# LV_supplies.net
KiCad netlist of a schematic drawn in Altium Designer
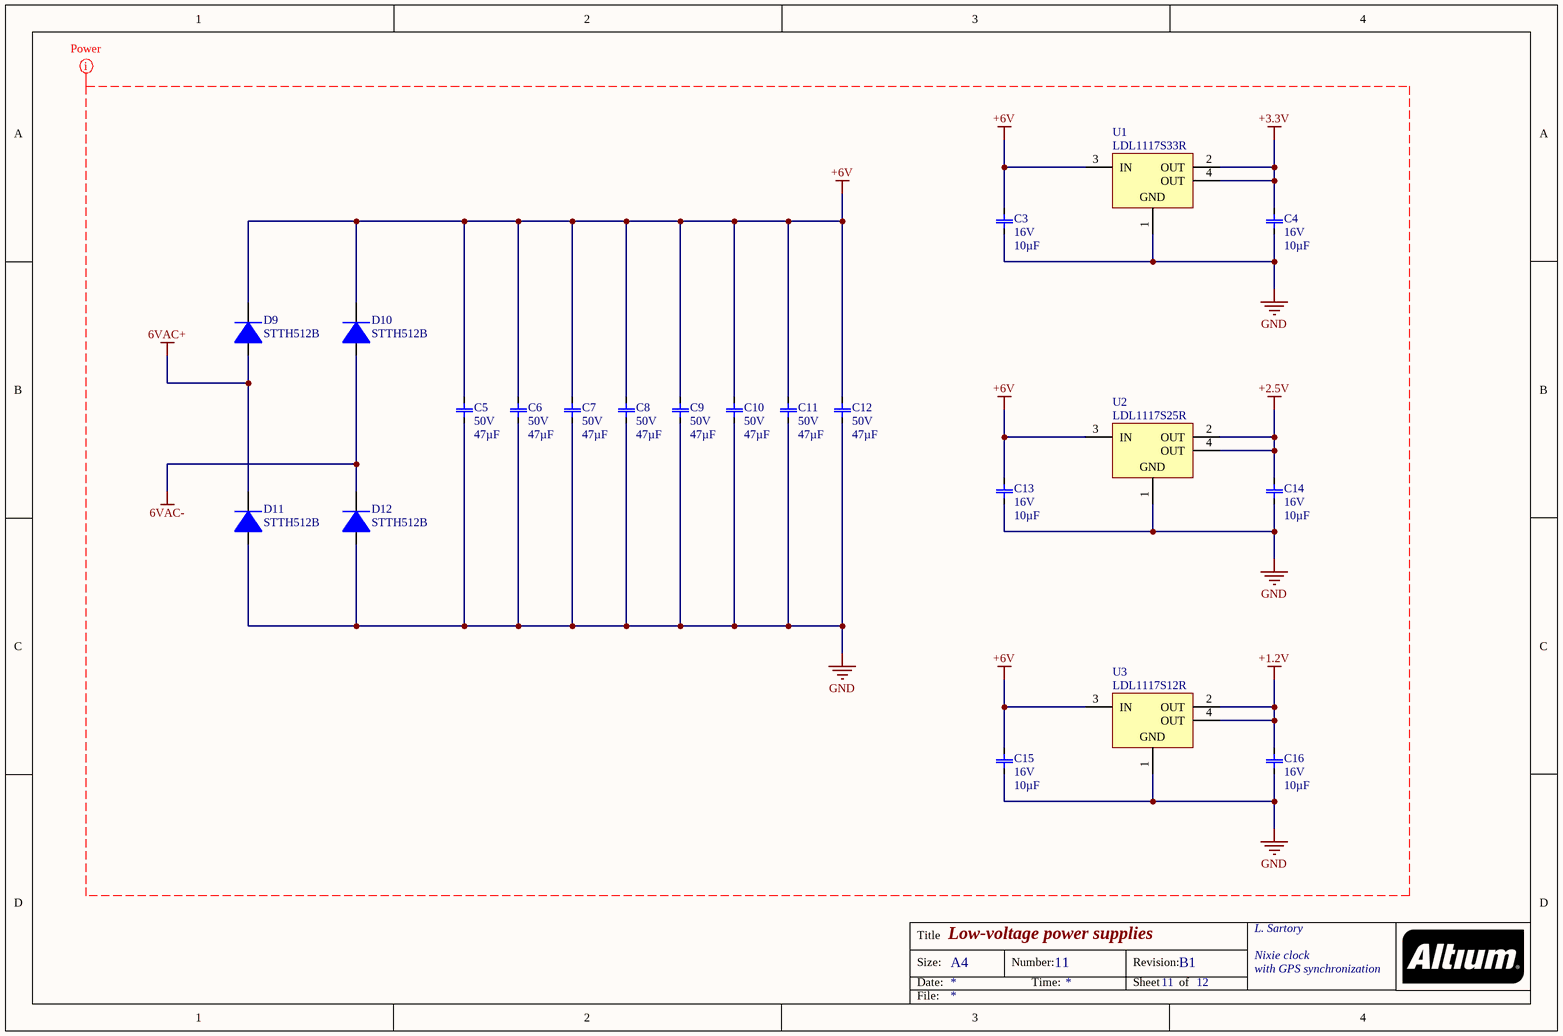
[diagram p0: LV_supplies.SchDoc]

(export (version "E")
  (design (tool "Eeschema 10.0.6"))
  (components
    (comp (ref "C3")
      (value "10µF")
      (footprint "MLCC_1210")
      (description "MLCC 10µF 16V 1210")
      (fields (field (name "VOLTAGE") "16V"))
      (libsource (lib "Nixie") (part "MLCC 10µF 16V 1210"))
    )
    (comp (ref "C4")
      (value "10µF")
      (footprint "MLCC_1210")
      (description "MLCC 10µF 16V 1210")
      (fields (field (name "VOLTAGE") "16V"))
      (libsource (lib "Nixie") (part "MLCC 10µF 16V 1210"))
    )
    (comp (ref "C5")
      (value "47µF")
      (footprint "MLCC_1210")
      (description "MLCC 47µF 50V 1210")
      (fields (field (name "VOLTAGE") "50V"))
      (libsource (lib "Nixie") (part "MLCC 47µF 50V 1210"))
    )
    (comp (ref "C6")
      (value "47µF")
      (footprint "MLCC_1210")
      (description "MLCC 47µF 50V 1210")
      (fields (field (name "VOLTAGE") "50V"))
      (libsource (lib "Nixie") (part "MLCC 47µF 50V 1210"))
    )
    (comp (ref "C7")
      (value "47µF")
      (footprint "MLCC_1210")
      (description "MLCC 47µF 50V 1210")
      (fields (field (name "VOLTAGE") "50V"))
      (libsource (lib "Nixie") (part "MLCC 47µF 50V 1210"))
    )
    (comp (ref "C8")
      (value "47µF")
      (footprint "MLCC_1210")
      (description "MLCC 47µF 50V 1210")
      (fields (field (name "VOLTAGE") "50V"))
      (libsource (lib "Nixie") (part "MLCC 47µF 50V 1210"))
    )
    (comp (ref "C9")
      (value "47µF")
      (footprint "MLCC_1210")
      (description "MLCC 47µF 50V 1210")
      (fields (field (name "VOLTAGE") "50V"))
      (libsource (lib "Nixie") (part "MLCC 47µF 50V 1210"))
    )
    (comp (ref "C10")
      (value "47µF")
      (footprint "MLCC_1210")
      (description "MLCC 47µF 50V 1210")
      (fields (field (name "VOLTAGE") "50V"))
      (libsource (lib "Nixie") (part "MLCC 47µF 50V 1210"))
    )
    (comp (ref "C11")
      (value "47µF")
      (footprint "MLCC_1210")
      (description "MLCC 47µF 50V 1210")
      (fields (field (name "VOLTAGE") "50V"))
      (libsource (lib "Nixie") (part "MLCC 47µF 50V 1210"))
    )
    (comp (ref "C12")
      (value "47µF")
      (footprint "MLCC_1210")
      (description "MLCC 47µF 50V 1210")
      (fields (field (name "VOLTAGE") "50V"))
      (libsource (lib "Nixie") (part "MLCC 47µF 50V 1210"))
    )
    (comp (ref "C13")
      (value "10µF")
      (footprint "MLCC_1210")
      (description "MLCC 10µF 16V 1210")
      (fields (field (name "VOLTAGE") "16V"))
      (libsource (lib "Nixie") (part "MLCC 10µF 16V 1210"))
    )
    (comp (ref "C14")
      (value "10µF")
      (footprint "MLCC_1210")
      (description "MLCC 10µF 16V 1210")
      (fields (field (name "VOLTAGE") "16V"))
      (libsource (lib "Nixie") (part "MLCC 10µF 16V 1210"))
    )
    (comp (ref "C15")
      (value "10µF")
      (footprint "MLCC_1210")
      (description "MLCC 10µF 16V 1210")
      (fields (field (name "VOLTAGE") "16V"))
      (libsource (lib "Nixie") (part "MLCC 10µF 16V 1210"))
    )
    (comp (ref "C16")
      (value "10µF")
      (footprint "MLCC_1210")
      (description "MLCC 10µF 16V 1210")
      (fields (field (name "VOLTAGE") "16V"))
      (libsource (lib "Nixie") (part "MLCC 10µF 16V 1210"))
    )
    (comp (ref "D9")
      (value "STTH512B")
      (footprint "STTH512B")
      (description "Ultrafast recovery - 1200 V diode")
      (libsource (lib "Nixie") (part "STTH512B"))
    )
    (comp (ref "D10")
      (value "STTH512B")
      (footprint "STTH512B")
      (description "Ultrafast recovery - 1200 V diode")
      (libsource (lib "Nixie") (part "STTH512B"))
    )
    (comp (ref "D11")
      (value "STTH512B")
      (footprint "STTH512B")
      (description "Ultrafast recovery - 1200 V diode")
      (libsource (lib "Nixie") (part "STTH512B"))
    )
    (comp (ref "D12")
      (value "STTH512B")
      (footprint "STTH512B")
      (description "Ultrafast recovery - 1200 V diode")
      (libsource (lib "Nixie") (part "STTH512B"))
    )
    (comp (ref "U1")
      (value "LDL1117S33R")
      (footprint "TLV1117")
      (description "Fixed LDO Voltage Regulator, 2.6 V to 18 V input, 75 mV Dropout, 3.3 V / 1.2 A out, SOT-223-4")
      (fields (field (name "PARTNUMBER") "TLV1117LV12DCYT") (field (name "MANUFACTURER") "Texas Instruments"))
      (libsource (lib "Nixie") (part "LDL1117S33R"))
    )
    (comp (ref "U2")
      (value "LDL1117S25R")
      (footprint "TLV1117")
      (description "Fixed LDO Voltage Regulator, 2.6 V to 18 V input, 75 mV Dropout, 2.5 V / 1.2 A out, SOT-223-4")
      (fields (field (name "MANUFACTURER") "Texas Instruments") (field (name "PARTNUMBER") "TLV1117LV25DCYT"))
      (libsource (lib "Nixie") (part "LDL1117S25R"))
    )
    (comp (ref "U3")
      (value "LDL1117S12R")
      (footprint "TLV1117")
      (description "Fixed LDO Voltage Regulator, 2.6 V to 18 V input, 170 mV Dropout, 1.2 V / 1.2 A out, SOT-223-4")
      (fields (field (name "MANUFACTURER") "Texas Instruments") (field (name "PARTNUMBER") "TLV1117LV30DCYT"))
      (libsource (lib "Nixie") (part "LDL1117S12R"))
    )
  )
  (nets
    (net (code "1") (name "+1.2V") (class "Default")
      (node (ref "C16") (pin "2") (pinfunction "2_2") (pintype "passive"))
      (node (ref "U3") (pin "2") (pinfunction "OUT_2") (pintype "power_in"))
      (node (ref "U3") (pin "4") (pinfunction "OUT_4") (pintype "power_in"))
    )
    (net (code "2") (name "+2.5V") (class "Default")
      (node (ref "C14") (pin "2") (pinfunction "2_2") (pintype "passive"))
      (node (ref "U2") (pin "2") (pinfunction "OUT_2") (pintype "power_in"))
      (node (ref "U2") (pin "4") (pinfunction "OUT_4") (pintype "power_in"))
    )
    (net (code "3") (name "+3.3V") (class "Default")
      (node (ref "C4") (pin "2") (pinfunction "2_2") (pintype "passive"))
      (node (ref "U1") (pin "2") (pinfunction "OUT_2") (pintype "power_in"))
      (node (ref "U1") (pin "4") (pinfunction "OUT_4") (pintype "power_in"))
    )
    (net (code "4") (name "+6V") (class "Default")
      (node (ref "C10") (pin "2") (pinfunction "2_2") (pintype "passive"))
      (node (ref "C11") (pin "2") (pinfunction "2_2") (pintype "passive"))
      (node (ref "C12") (pin "2") (pinfunction "2_2") (pintype "passive"))
      (node (ref "C13") (pin "2") (pinfunction "2_2") (pintype "passive"))
      (node (ref "C15") (pin "2") (pinfunction "2_2") (pintype "passive"))
      (node (ref "C3") (pin "2") (pinfunction "2_2") (pintype "passive"))
      (node (ref "C5") (pin "2") (pinfunction "2_2") (pintype "passive"))
      (node (ref "C6") (pin "2") (pinfunction "2_2") (pintype "passive"))
      (node (ref "C7") (pin "2") (pinfunction "2_2") (pintype "passive"))
      (node (ref "C8") (pin "2") (pinfunction "2_2") (pintype "passive"))
      (node (ref "C9") (pin "2") (pinfunction "2_2") (pintype "passive"))
      (node (ref "D10") (pin "K") (pinfunction "K_K") (pintype "passive"))
      (node (ref "D9") (pin "K") (pinfunction "K_K") (pintype "passive"))
      (node (ref "U1") (pin "3") (pinfunction "IN_3") (pintype "power_in"))
      (node (ref "U2") (pin "3") (pinfunction "IN_3") (pintype "power_in"))
      (node (ref "U3") (pin "3") (pinfunction "IN_3") (pintype "power_in"))
    )
    (net (code "5") (name "6VAC+") (class "Default")
      (node (ref "D11") (pin "K") (pinfunction "K_K") (pintype "passive"))
      (node (ref "D9") (pin "A") (pinfunction "A_A") (pintype "passive"))
    )
    (net (code "6") (name "6VAC-") (class "Default")
      (node (ref "D10") (pin "A") (pinfunction "A_A") (pintype "passive"))
      (node (ref "D12") (pin "K") (pinfunction "K_K") (pintype "passive"))
    )
    (net (code "7") (name "GND") (class "Default")
      (node (ref "C10") (pin "1") (pinfunction "1_1") (pintype "passive"))
      (node (ref "C11") (pin "1") (pinfunction "1_1") (pintype "passive"))
      (node (ref "C12") (pin "1") (pinfunction "1_1") (pintype "passive"))
      (node (ref "C13") (pin "1") (pinfunction "1_1") (pintype "passive"))
      (node (ref "C14") (pin "1") (pinfunction "1_1") (pintype "passive"))
      (node (ref "C15") (pin "1") (pinfunction "1_1") (pintype "passive"))
      (node (ref "C16") (pin "1") (pinfunction "1_1") (pintype "passive"))
      (node (ref "C3") (pin "1") (pinfunction "1_1") (pintype "passive"))
      (node (ref "C4") (pin "1") (pinfunction "1_1") (pintype "passive"))
      (node (ref "C5") (pin "1") (pinfunction "1_1") (pintype "passive"))
      (node (ref "C6") (pin "1") (pinfunction "1_1") (pintype "passive"))
      (node (ref "C7") (pin "1") (pinfunction "1_1") (pintype "passive"))
      (node (ref "C8") (pin "1") (pinfunction "1_1") (pintype "passive"))
      (node (ref "C9") (pin "1") (pinfunction "1_1") (pintype "passive"))
      (node (ref "D11") (pin "A") (pinfunction "A_A") (pintype "passive"))
      (node (ref "D12") (pin "A") (pinfunction "A_A") (pintype "passive"))
      (node (ref "U1") (pin "1") (pinfunction "GND_1") (pintype "power_in"))
      (node (ref "U2") (pin "1") (pinfunction "GND_1") (pintype "power_in"))
      (node (ref "U3") (pin "1") (pinfunction "GND_1") (pintype "power_in"))
    )
  )
)
